# pcb_univ_3-_2-7_-_5-0_-x-rev3.net
KiCad netlist of a schematic drawn in EAGLE
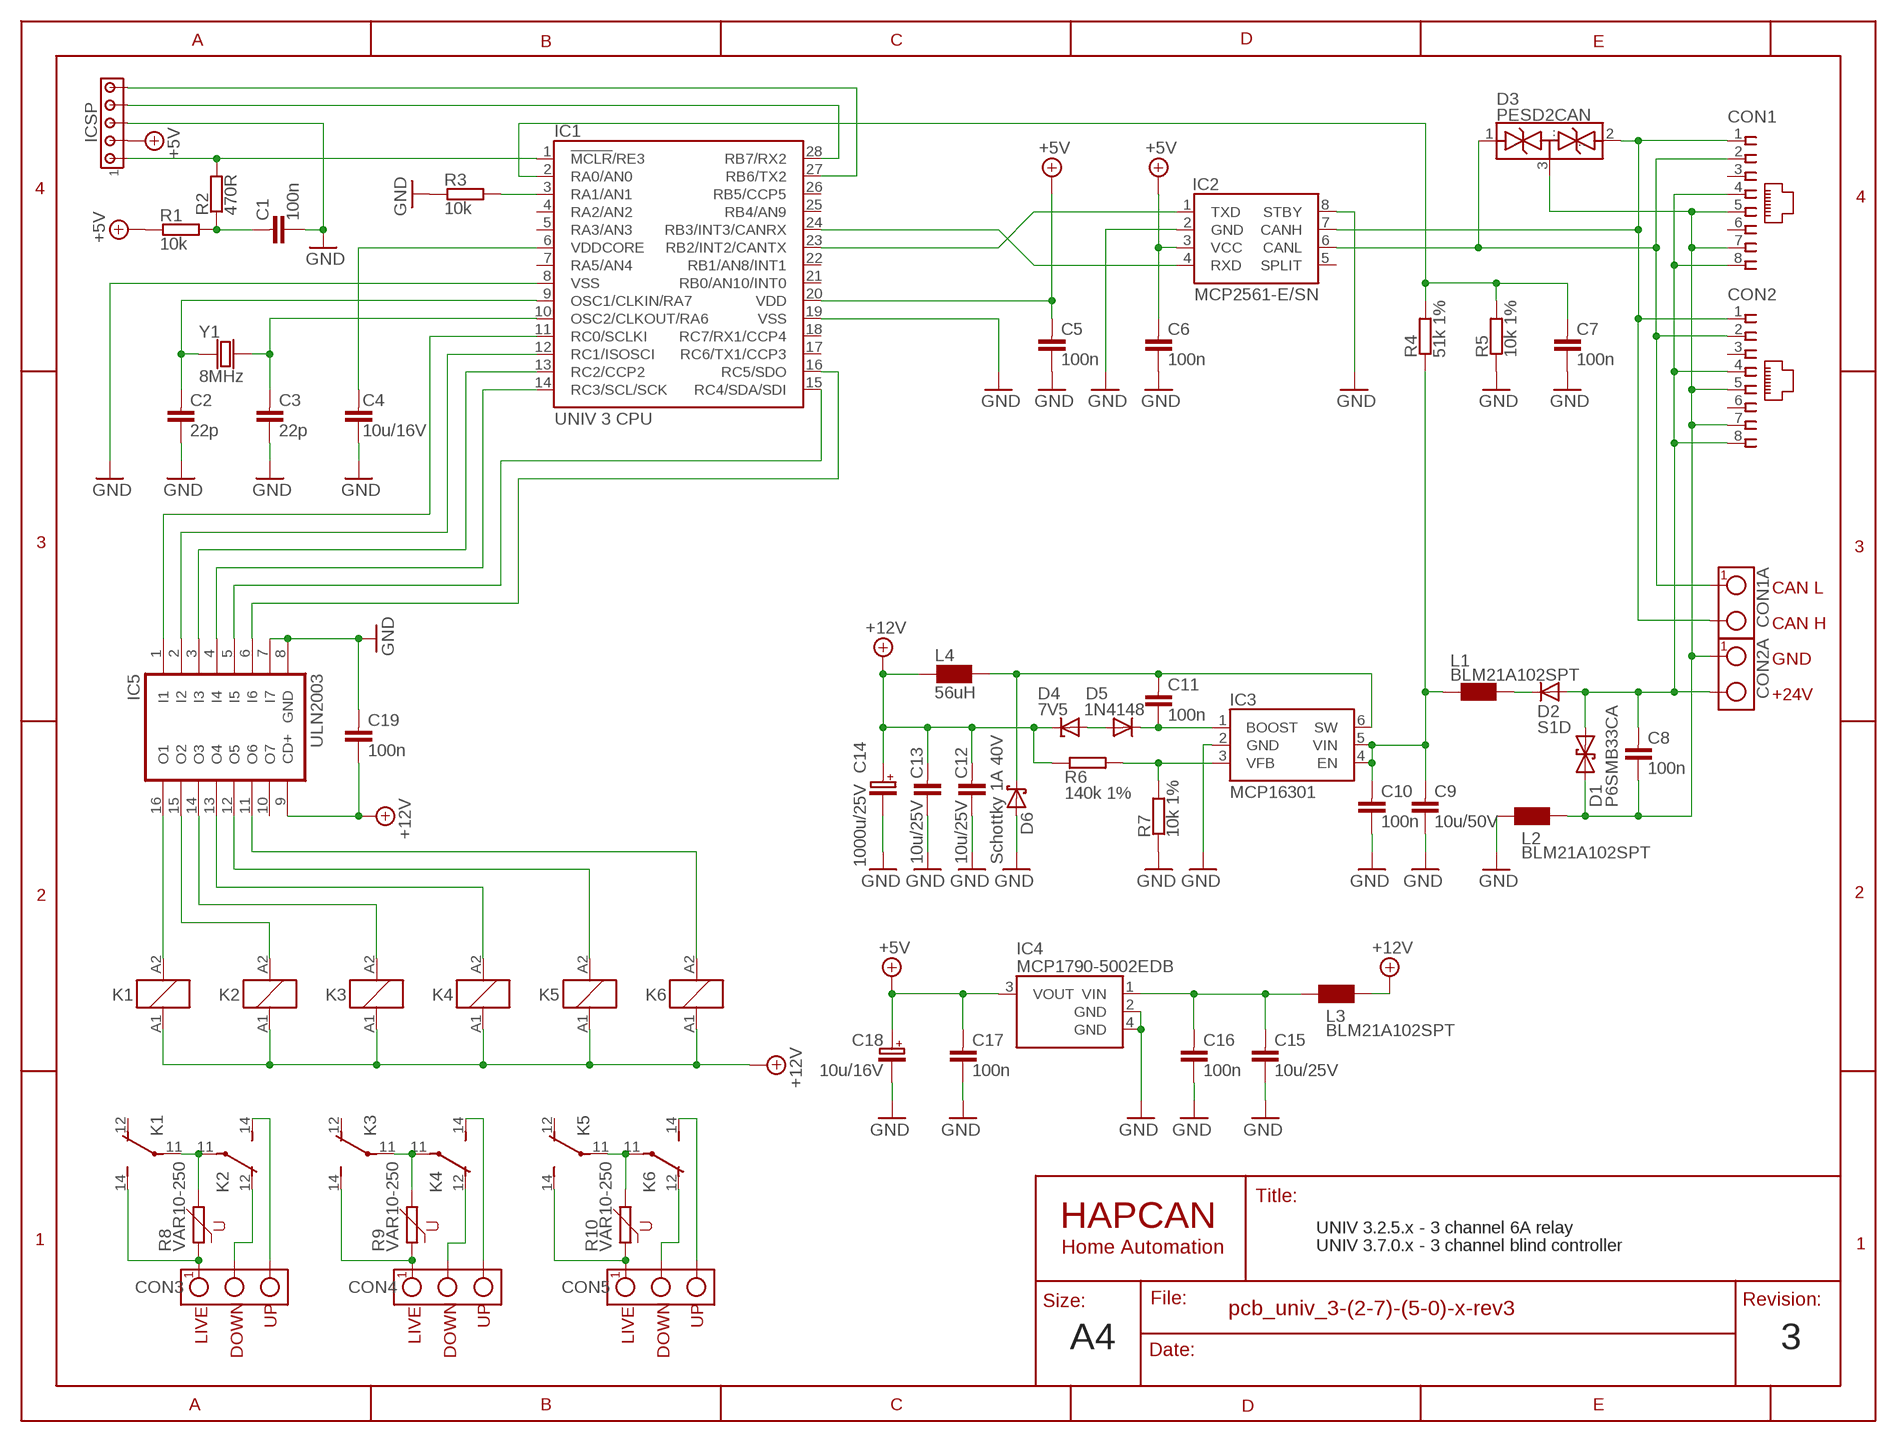
[diagram p0: schematic, sheet 1]

(export (version "E")
  (design (tool "Eeschema 10.0.6"))
  (components
    (comp (ref "C1")
      (value "100n")
      (footprint "eagle-import:0805")
      (libsource (lib "eagle-import") (part "CAPACITOR0805"))
    )
    (comp (ref "C2")
      (value "22p")
      (footprint "eagle-import:0805")
      (libsource (lib "eagle-import") (part "CAPACITOR0805"))
    )
    (comp (ref "C3")
      (value "22p")
      (footprint "eagle-import:0805")
      (libsource (lib "eagle-import") (part "CAPACITOR0805"))
    )
    (comp (ref "C4")
      (value "10u/16V")
      (footprint "eagle-import:0805")
      (libsource (lib "eagle-import") (part "CAPACITOR0805"))
    )
    (comp (ref "C5")
      (value "100n")
      (footprint "eagle-import:0805")
      (libsource (lib "eagle-import") (part "CAPACITOR0805"))
    )
    (comp (ref "C6")
      (value "100n")
      (footprint "eagle-import:0805")
      (libsource (lib "eagle-import") (part "CAPACITOR0805"))
    )
    (comp (ref "C7")
      (value "100n")
      (footprint "eagle-import:0805")
      (libsource (lib "eagle-import") (part "CAPACITOR0805"))
    )
    (comp (ref "C8")
      (value "100n")
      (footprint "eagle-import:0805")
      (libsource (lib "eagle-import") (part "CAPACITOR0805"))
    )
    (comp (ref "C9")
      (value "10u/50V")
      (footprint "eagle-import:1210")
      (libsource (lib "eagle-import") (part "CAPACITOR1210"))
    )
    (comp (ref "C10")
      (value "100n")
      (footprint "eagle-import:0805")
      (libsource (lib "eagle-import") (part "CAPACITOR0805"))
    )
    (comp (ref "C11")
      (value "100n")
      (footprint "eagle-import:0805")
      (libsource (lib "eagle-import") (part "CAPACITOR0805"))
    )
    (comp (ref "C12")
      (value "10u/25V")
      (footprint "eagle-import:1206")
      (libsource (lib "eagle-import") (part "CAPACITOR1206"))
    )
    (comp (ref "C13")
      (value "10u/25V")
      (footprint "eagle-import:1206")
      (libsource (lib "eagle-import") (part "CAPACITOR1206"))
    )
    (comp (ref "C14")
      (value "1000u/25V")
      (footprint "eagle-import:CAP-5X10.5")
      (libsource (lib "eagle-import") (part "CAPACITOR-POLARIZED-5X10.5"))
    )
    (comp (ref "C15")
      (value "10u/25V")
      (footprint "eagle-import:1206")
      (libsource (lib "eagle-import") (part "CAPACITOR1206"))
    )
    (comp (ref "C16")
      (value "100n")
      (footprint "eagle-import:0805")
      (libsource (lib "eagle-import") (part "CAPACITOR0805"))
    )
    (comp (ref "C17")
      (value "100n")
      (footprint "eagle-import:0805")
      (libsource (lib "eagle-import") (part "CAPACITOR0805"))
    )
    (comp (ref "C18")
      (value "10u/16V")
      (footprint "eagle-import:SMC_B")
      (libsource (lib "eagle-import") (part "CAPACITOR-POLARIZED-SMC_B"))
    )
    (comp (ref "C19")
      (value "100n")
      (footprint "eagle-import:0805")
      (libsource (lib "eagle-import") (part "CAPACITOR0805"))
    )
    (comp (ref "CON1")
      (value "RJ45-SOCKET")
      (footprint "eagle-import:RJ45-PCB-SOCKET")
      (libsource (lib "eagle-import") (part "RJ45-SOCKET"))
    )
    (comp (ref "CON1A")
      (value "TERMINAL-2")
      (footprint "eagle-import:ARK2-5X10,5MM")
      (libsource (lib "eagle-import") (part "TERMINAL-2-5X10,5MM"))
    )
    (comp (ref "CON2")
      (value "RJ45-SOCKET")
      (footprint "eagle-import:RJ45-PCB-SOCKET")
      (libsource (lib "eagle-import") (part "RJ45-SOCKET"))
    )
    (comp (ref "CON2A")
      (value "TERMINAL-2")
      (footprint "eagle-import:ARK2-5X10,5MM")
      (libsource (lib "eagle-import") (part "TERMINAL-2-5X10,5MM"))
    )
    (comp (ref "CON3")
      (value "TERMINAL-3-5X10.5MM")
      (footprint "eagle-import:ARK3-5X10.5MM")
      (libsource (lib "eagle-import") (part "TERMINAL-3-5X10.5MM"))
    )
    (comp (ref "CON4")
      (value "TERMINAL-3-5X10.5MM")
      (footprint "eagle-import:ARK3-5X10.5MM")
      (libsource (lib "eagle-import") (part "TERMINAL-3-5X10.5MM"))
    )
    (comp (ref "CON5")
      (value "TERMINAL-3-5X10.5MM")
      (footprint "eagle-import:ARK3-5X10.5MM")
      (libsource (lib "eagle-import") (part "TERMINAL-3-5X10.5MM"))
    )
    (comp (ref "D1")
      (value "P6SMB33CA")
      (footprint "eagle-import:DO-214_TRANSIL2")
      (libsource (lib "eagle-import") (part "DIODE_TRANSIL2"))
    )
    (comp (ref "D2")
      (value "S1D")
      (footprint "eagle-import:DO-214")
      (libsource (lib "eagle-import") (part "DIODE_DO-214"))
    )
    (comp (ref "D3")
      (value "PESD2CAN")
      (footprint "eagle-import:SOT-23")
      (libsource (lib "eagle-import") (part "PESD2CANSOT-23"))
    )
    (comp (ref "D4")
      (value "7V5")
      (footprint "eagle-import:SOD-80")
      (libsource (lib "eagle-import") (part "DIODE_ZENER_SOD-80"))
    )
    (comp (ref "D5")
      (value "1N4148")
      (footprint "eagle-import:0805")
      (libsource (lib "eagle-import") (part "DIODE_0805"))
    )
    (comp (ref "D6")
      (value "Schottky 1A 40V")
      (footprint "eagle-import:DO-214")
      (libsource (lib "eagle-import") (part "DIODE_TRANSIL1_DO214"))
    )
    (comp (ref "IC1")
      (value "UNIV 3 CPU")
      (footprint "eagle-import:UNIV3CPU")
      (libsource (lib "eagle-import") (part "UNIV3CPU-I/SO"))
    )
    (comp (ref "IC2")
      (value "MCP2561-E/SN")
      (footprint "eagle-import:SO-08")
      (libsource (lib "eagle-import") (part "MCP2561-E/SN"))
    )
    (comp (ref "IC3")
      (value "MCP16301")
      (footprint "eagle-import:SOT-23-6")
      (libsource (lib "eagle-import") (part "MCP16301SOT23-6"))
    )
    (comp (ref "IC4")
      (value "MCP1790-5002EDB")
      (footprint "eagle-import:SOT-223")
      (libsource (lib "eagle-import") (part "MCP1826SOT223-3"))
    )
    (comp (ref "IC5")
      (value "ULN2003")
      (footprint "eagle-import:SO-16")
      (libsource (lib "eagle-import") (part "ULN2003"))
    )
    (comp (ref "ICSP")
      (value "HEADER5")
      (footprint "eagle-import:SIP-5")
      (libsource (lib "eagle-import") (part "HEADER5"))
    )
    (comp (ref "K1")
      (value "RELAY_SNR_SPDTV")
      (footprint "eagle-import:RELAY_SNR_SPDT_V")
      (libsource (lib "eagle-import") (part "RELAY_SNR_SPDTV"))
    )
    (comp (ref "K2")
      (value "RELAY_SNR_SPDTV")
      (footprint "eagle-import:RELAY_SNR_SPDT_V")
      (libsource (lib "eagle-import") (part "RELAY_SNR_SPDTV"))
    )
    (comp (ref "K3")
      (value "RELAY_SNR_SPDTV")
      (footprint "eagle-import:RELAY_SNR_SPDT_V")
      (libsource (lib "eagle-import") (part "RELAY_SNR_SPDTV"))
    )
    (comp (ref "K4")
      (value "RELAY_SNR_SPDTV")
      (footprint "eagle-import:RELAY_SNR_SPDT_V")
      (libsource (lib "eagle-import") (part "RELAY_SNR_SPDTV"))
    )
    (comp (ref "K5")
      (value "RELAY_SNR_SPDTV")
      (footprint "eagle-import:RELAY_SNR_SPDT_V")
      (libsource (lib "eagle-import") (part "RELAY_SNR_SPDTV"))
    )
    (comp (ref "K6")
      (value "RELAY_SNR_SPDTV")
      (footprint "eagle-import:RELAY_SNR_SPDT_V")
      (libsource (lib "eagle-import") (part "RELAY_SNR_SPDTV"))
    )
    (comp (ref "L1")
      (value "BLM21A102SPT")
      (footprint "eagle-import:0805")
      (libsource (lib "eagle-import") (part "CHOKE0805"))
    )
    (comp (ref "L2")
      (value "BLM21A102SPT")
      (footprint "eagle-import:0805")
      (libsource (lib "eagle-import") (part "CHOKE0805"))
    )
    (comp (ref "L3")
      (value "BLM21A102SPT")
      (footprint "eagle-import:0805")
      (libsource (lib "eagle-import") (part "CHOKE0805"))
    )
    (comp (ref "L4")
      (value "56uH")
      (footprint "eagle-import:CHOKE-DER0705")
      (libsource (lib "eagle-import") (part "CHOKEDER0705"))
    )
    (comp (ref "R1")
      (value "10k")
      (footprint "eagle-import:0805")
      (libsource (lib "eagle-import") (part "RESISTOR0805"))
    )
    (comp (ref "R2")
      (value "470R")
      (footprint "eagle-import:0805")
      (libsource (lib "eagle-import") (part "RESISTOR0805"))
    )
    (comp (ref "R3")
      (value "10k")
      (footprint "eagle-import:0805")
      (libsource (lib "eagle-import") (part "RESISTOR0805"))
    )
    (comp (ref "R4")
      (value "51k 1%")
      (footprint "eagle-import:0805")
      (libsource (lib "eagle-import") (part "RESISTOR0805"))
    )
    (comp (ref "R5")
      (value "10k 1%")
      (footprint "eagle-import:0805")
      (libsource (lib "eagle-import") (part "RESISTOR0805"))
    )
    (comp (ref "R6")
      (value "140k 1%")
      (footprint "eagle-import:0805")
      (libsource (lib "eagle-import") (part "RESISTOR0805"))
    )
    (comp (ref "R7")
      (value "10k 1%")
      (footprint "eagle-import:0805")
      (libsource (lib "eagle-import") (part "RESISTOR0805"))
    )
    (comp (ref "R8")
      (value "VAR10-250")
      (footprint "eagle-import:VARISTOR1")
      (libsource (lib "eagle-import") (part "VARISTOR7.5MM-1"))
    )
    (comp (ref "R9")
      (value "VAR10-250")
      (footprint "eagle-import:VARISTOR1")
      (libsource (lib "eagle-import") (part "VARISTOR7.5MM-1"))
    )
    (comp (ref "R10")
      (value "VAR10-250")
      (footprint "eagle-import:VARISTOR1")
      (libsource (lib "eagle-import") (part "VARISTOR7.5MM-1"))
    )
    (comp (ref "Y1")
      (value "8MHz")
      (footprint "eagle-import:CRYSTAL-HC49V")
      (libsource (lib "eagle-import") (part "CRYSTAL-HC49V"))
    )
  )
  (nets
    (net (code "1") (name "+5V") (class "Default")
      (node (ref "C17") (pin "1") (pinfunction "1_1") (pintype "passive"))
      (node (ref "C18") (pin "+") (pinfunction "1_+") (pintype "passive"))
      (node (ref "C5") (pin "1") (pinfunction "1_1") (pintype "passive"))
      (node (ref "C6") (pin "1") (pinfunction "1_1") (pintype "passive"))
      (node (ref "IC1") (pin "20") (pinfunction "VDD_20") (pintype "bidirectional"))
      (node (ref "IC2") (pin "3") (pinfunction "VCC_3") (pintype "bidirectional"))
      (node (ref "IC4") (pin "3") (pinfunction "VOUT_3") (pintype "bidirectional"))
      (node (ref "ICSP") (pin "2") (pinfunction "2_2") (pintype "passive"))
      (node (ref "R1") (pin "1") (pinfunction "1_1") (pintype "passive"))
    )
    (net (code "2") (name "+12V") (class "Default")
      (node (ref "C12") (pin "1") (pinfunction "1_1") (pintype "passive"))
      (node (ref "C13") (pin "1") (pinfunction "1_1") (pintype "passive"))
      (node (ref "C14") (pin "+") (pinfunction "1_+") (pintype "passive"))
      (node (ref "C19") (pin "2") (pinfunction "2_2") (pintype "passive"))
      (node (ref "D4") (pin "C") (pinfunction "C_C") (pintype "passive"))
      (node (ref "IC5") (pin "9") (pinfunction "CD+_9") (pintype "passive"))
      (node (ref "K1") (pin "A1") (pinfunction "1_A1") (pintype "passive"))
      (node (ref "K2") (pin "A1") (pinfunction "1_A1") (pintype "passive"))
      (node (ref "K3") (pin "A1") (pinfunction "1_A1") (pintype "passive"))
      (node (ref "K4") (pin "A1") (pinfunction "1_A1") (pintype "passive"))
      (node (ref "K5") (pin "A1") (pinfunction "1_A1") (pintype "passive"))
      (node (ref "K6") (pin "A1") (pinfunction "1_A1") (pintype "passive"))
      (node (ref "L3") (pin "2") (pinfunction "2_2") (pintype "passive"))
      (node (ref "L4") (pin "1") (pinfunction "1_1") (pintype "passive"))
      (node (ref "R6") (pin "1") (pinfunction "1_1") (pintype "passive"))
    )
    (net (code "3") (name "GND") (class "Default")
      (node (ref "C1") (pin "2") (pinfunction "2_2") (pintype "passive"))
      (node (ref "C10") (pin "2") (pinfunction "2_2") (pintype "passive"))
      (node (ref "C12") (pin "2") (pinfunction "2_2") (pintype "passive"))
      (node (ref "C13") (pin "2") (pinfunction "2_2") (pintype "passive"))
      (node (ref "C14") (pin "-") (pinfunction "2_-") (pintype "passive"))
      (node (ref "C15") (pin "2") (pinfunction "2_2") (pintype "passive"))
      (node (ref "C16") (pin "2") (pinfunction "2_2") (pintype "passive"))
      (node (ref "C17") (pin "2") (pinfunction "2_2") (pintype "passive"))
      (node (ref "C18") (pin "-") (pinfunction "2_-") (pintype "passive"))
      (node (ref "C19") (pin "1") (pinfunction "1_1") (pintype "passive"))
      (node (ref "C2") (pin "2") (pinfunction "2_2") (pintype "passive"))
      (node (ref "C3") (pin "2") (pinfunction "2_2") (pintype "passive"))
      (node (ref "C4") (pin "2") (pinfunction "2_2") (pintype "passive"))
      (node (ref "C5") (pin "2") (pinfunction "2_2") (pintype "passive"))
      (node (ref "C6") (pin "2") (pinfunction "2_2") (pintype "passive"))
      (node (ref "C7") (pin "2") (pinfunction "2_2") (pintype "passive"))
      (node (ref "C9") (pin "2") (pinfunction "2_2") (pintype "passive"))
      (node (ref "D6") (pin "A") (pinfunction "A_A") (pintype "passive"))
      (node (ref "IC1") (pin "19") (pinfunction "VSS_19") (pintype "bidirectional"))
      (node (ref "IC1") (pin "8") (pinfunction "VSS_8") (pintype "bidirectional"))
      (node (ref "IC2") (pin "2") (pinfunction "GND_2") (pintype "bidirectional"))
      (node (ref "IC2") (pin "8") (pinfunction "STBY_8") (pintype "bidirectional"))
      (node (ref "IC3") (pin "2") (pinfunction "GND_2") (pintype "bidirectional"))
      (node (ref "IC4") (pin "2") (pinfunction "GND_2") (pintype "bidirectional"))
      (node (ref "IC4") (pin "4") (pinfunction "GND_4") (pintype "bidirectional"))
      (node (ref "IC5") (pin "7") (pinfunction "I7_7") (pintype "input"))
      (node (ref "IC5") (pin "8") (pinfunction "GND_8") (pintype "power_in"))
      (node (ref "ICSP") (pin "3") (pinfunction "3_3") (pintype "passive"))
      (node (ref "L2") (pin "1") (pinfunction "1_1") (pintype "passive"))
      (node (ref "R3") (pin "1") (pinfunction "1_1") (pintype "passive"))
      (node (ref "R5") (pin "1") (pinfunction "1_1") (pintype "passive"))
      (node (ref "R7") (pin "1") (pinfunction "1_1") (pintype "passive"))
    )
    (net (code "4") (name "Net-(C1-Pad1)") (class "Default")
      (node (ref "C1") (pin "1") (pinfunction "1_1") (pintype "passive"))
      (node (ref "R1") (pin "2") (pinfunction "2_2") (pintype "passive"))
      (node (ref "R2") (pin "1") (pinfunction "1_1") (pintype "passive"))
    )
    (net (code "5") (name "Net-(D1-1)") (class "Default")
      (node (ref "C8") (pin "2") (pinfunction "2_2") (pintype "passive"))
      (node (ref "CON1") (pin "5") (pinfunction "5_5") (pintype "passive"))
      (node (ref "CON1") (pin "7") (pinfunction "7_7") (pintype "passive"))
      (node (ref "CON2") (pin "5") (pinfunction "5_5") (pintype "passive"))
      (node (ref "CON2") (pin "7") (pinfunction "7_7") (pintype "passive"))
      (node (ref "CON2A") (pin "1") (pinfunction "1_1") (pintype "passive"))
      (node (ref "D1") (pin "A") (pinfunction "1_A") (pintype "passive"))
      (node (ref "D3") (pin "3") (pinfunction "..._3") (pintype "bidirectional"))
      (node (ref "L2") (pin "2") (pinfunction "2_2") (pintype "passive"))
    )
    (net (code "6") (name "Net-(D1-2)") (class "Default")
      (node (ref "C8") (pin "1") (pinfunction "1_1") (pintype "passive"))
      (node (ref "CON1") (pin "4") (pinfunction "4_4") (pintype "passive"))
      (node (ref "CON1") (pin "8") (pinfunction "8_8") (pintype "passive"))
      (node (ref "CON2") (pin "4") (pinfunction "4_4") (pintype "passive"))
      (node (ref "CON2") (pin "8") (pinfunction "8_8") (pintype "passive"))
      (node (ref "CON2A") (pin "2") (pinfunction "2_2") (pintype "passive"))
      (node (ref "D1") (pin "C") (pinfunction "2_C") (pintype "passive"))
      (node (ref "D2") (pin "A") (pinfunction "A_A") (pintype "passive"))
    )
    (net (code "7") (name "Net-(D2-PadC)") (class "Default")
      (node (ref "D2") (pin "C") (pinfunction "C_C") (pintype "passive"))
      (node (ref "L1") (pin "2") (pinfunction "2_2") (pintype "passive"))
    )
    (net (code "8") (name "Net-(D3-.)") (class "Default")
      (node (ref "CON1") (pin "2") (pinfunction "2_2") (pintype "passive"))
      (node (ref "CON1A") (pin "1") (pinfunction "1_1") (pintype "passive"))
      (node (ref "CON2") (pin "2") (pinfunction "2_2") (pintype "passive"))
      (node (ref "D3") (pin "1") (pinfunction "._1") (pintype "bidirectional"))
      (node (ref "IC2") (pin "6") (pinfunction "CANL_6") (pintype "bidirectional"))
    )
    (net (code "9") (name "Net-(D3-..)") (class "Default")
      (node (ref "CON1") (pin "1") (pinfunction "1_1") (pintype "passive"))
      (node (ref "CON1A") (pin "2") (pinfunction "2_2") (pintype "passive"))
      (node (ref "CON2") (pin "1") (pinfunction "1_1") (pintype "passive"))
      (node (ref "D3") (pin "2") (pinfunction ".._2") (pintype "bidirectional"))
      (node (ref "IC2") (pin "7") (pinfunction "CANH_7") (pintype "bidirectional"))
    )
    (net (code "10") (name "Net-(D5-A)") (class "Default")
      (node (ref "D4") (pin "A") (pinfunction "A_A") (pintype "passive"))
      (node (ref "D5") (pin "2") (pinfunction "A_2") (pintype "passive"))
    )
    (net (code "11") (name "Net-(D5-C)") (class "Default")
      (node (ref "C11") (pin "2") (pinfunction "2_2") (pintype "passive"))
      (node (ref "D5") (pin "1") (pinfunction "C_1") (pintype "passive"))
      (node (ref "IC3") (pin "1") (pinfunction "BOOST_1") (pintype "bidirectional"))
    )
    (net (code "12") (name "Net-(IC1-OSC1{slash}CLKIN{slash}RA7)") (class "Default")
      (node (ref "C2") (pin "1") (pinfunction "1_1") (pintype "passive"))
      (node (ref "IC1") (pin "9") (pinfunction "OSC1/CLKIN/RA7_9") (pintype "bidirectional"))
      (node (ref "Y1") (pin "1") (pinfunction "1_1") (pintype "passive"))
    )
    (net (code "13") (name "Net-(IC1-OSC2{slash}CLKOUT{slash}RA6)") (class "Default")
      (node (ref "C3") (pin "1") (pinfunction "1_1") (pintype "passive"))
      (node (ref "IC1") (pin "10") (pinfunction "OSC2/CLKOUT/RA6_10") (pintype "bidirectional"))
      (node (ref "Y1") (pin "2") (pinfunction "2_2") (pintype "passive"))
    )
    (net (code "14") (name "Net-(IC1-RA0{slash}AN0)") (class "Default")
      (node (ref "C7") (pin "1") (pinfunction "1_1") (pintype "passive"))
      (node (ref "IC1") (pin "2") (pinfunction "RA0/AN0_2") (pintype "bidirectional"))
      (node (ref "R4") (pin "2") (pinfunction "2_2") (pintype "passive"))
      (node (ref "R5") (pin "2") (pinfunction "2_2") (pintype "passive"))
    )
    (net (code "15") (name "Net-(IC1-RA1{slash}AN1)") (class "Default")
      (node (ref "IC1") (pin "3") (pinfunction "RA1/AN1_3") (pintype "bidirectional"))
      (node (ref "R3") (pin "2") (pinfunction "2_2") (pintype "passive"))
    )
    (net (code "16") (name "Net-(IC1-RB2{slash}INT2{slash}CANTX)") (class "Default")
      (node (ref "IC1") (pin "23") (pinfunction "RB2/INT2/CANTX_23") (pintype "bidirectional"))
      (node (ref "IC2") (pin "1") (pinfunction "TXD_1") (pintype "bidirectional"))
    )
    (net (code "17") (name "Net-(IC1-RB3{slash}INT3{slash}CANRX)") (class "Default")
      (node (ref "IC1") (pin "24") (pinfunction "RB3/INT3/CANRX_24") (pintype "bidirectional"))
      (node (ref "IC2") (pin "4") (pinfunction "RXD_4") (pintype "bidirectional"))
    )
    (net (code "18") (name "Net-(IC1-RB6{slash}TX2)") (class "Default")
      (node (ref "IC1") (pin "27") (pinfunction "RB6/TX2_27") (pintype "bidirectional"))
      (node (ref "ICSP") (pin "5") (pinfunction "5_5") (pintype "passive"))
    )
    (net (code "19") (name "Net-(IC1-RB7{slash}RX2)") (class "Default")
      (node (ref "IC1") (pin "28") (pinfunction "RB7/RX2_28") (pintype "bidirectional"))
      (node (ref "ICSP") (pin "4") (pinfunction "4_4") (pintype "passive"))
    )
    (net (code "20") (name "Net-(IC1-RC0{slash}SCLKI)") (class "Default")
      (node (ref "IC1") (pin "11") (pinfunction "RC0/SCLKI_11") (pintype "bidirectional"))
      (node (ref "IC5") (pin "1") (pinfunction "I1_1") (pintype "input"))
    )
    (net (code "21") (name "Net-(IC1-RC1{slash}ISOSCI)") (class "Default")
      (node (ref "IC1") (pin "12") (pinfunction "RC1/ISOSCI_12") (pintype "bidirectional"))
      (node (ref "IC5") (pin "2") (pinfunction "I2_2") (pintype "input"))
    )
    (net (code "22") (name "Net-(IC1-RC2{slash}CCP2)") (class "Default")
      (node (ref "IC1") (pin "13") (pinfunction "RC2/CCP2_13") (pintype "bidirectional"))
      (node (ref "IC5") (pin "3") (pinfunction "I3_3") (pintype "input"))
    )
    (net (code "23") (name "Net-(IC1-RC3{slash}SCL{slash}SCK)") (class "Default")
      (node (ref "IC1") (pin "14") (pinfunction "RC3/SCL/SCK_14") (pintype "bidirectional"))
      (node (ref "IC5") (pin "4") (pinfunction "I4_4") (pintype "input"))
    )
    (net (code "24") (name "Net-(IC1-RC4{slash}SDA{slash}SDI)") (class "Default")
      (node (ref "IC1") (pin "15") (pinfunction "RC4/SDA/SDI_15") (pintype "bidirectional"))
      (node (ref "IC5") (pin "5") (pinfunction "I5_5") (pintype "input"))
    )
    (net (code "25") (name "Net-(IC1-RC5{slash}SDO)") (class "Default")
      (node (ref "IC1") (pin "16") (pinfunction "RC5/SDO_16") (pintype "bidirectional"))
      (node (ref "IC5") (pin "6") (pinfunction "I6_6") (pintype "input"))
    )
    (net (code "26") (name "Net-(IC1-VDDCORE)") (class "Default")
      (node (ref "C4") (pin "1") (pinfunction "1_1") (pintype "passive"))
      (node (ref "IC1") (pin "6") (pinfunction "VDDCORE_6") (pintype "bidirectional"))
    )
    (net (code "27") (name "Net-(IC1-~{MCLR}{slash}RE3)") (class "Default")
      (node (ref "IC1") (pin "1") (pinfunction "~{MCLR}/RE3_1") (pintype "bidirectional"))
      (node (ref "ICSP") (pin "1") (pinfunction "1_1") (pintype "passive"))
      (node (ref "R2") (pin "2") (pinfunction "2_2") (pintype "passive"))
    )
    (net (code "28") (name "Net-(IC3-EN)") (class "Default")
      (node (ref "C10") (pin "1") (pinfunction "1_1") (pintype "passive"))
      (node (ref "C9") (pin "1") (pinfunction "1_1") (pintype "passive"))
      (node (ref "IC3") (pin "4") (pinfunction "EN_4") (pintype "bidirectional"))
      (node (ref "IC3") (pin "5") (pinfunction "VIN_5") (pintype "bidirectional"))
      (node (ref "L1") (pin "1") (pinfunction "1_1") (pintype "passive"))
      (node (ref "R4") (pin "1") (pinfunction "1_1") (pintype "passive"))
    )
    (net (code "29") (name "Net-(IC3-SW)") (class "Default")
      (node (ref "C11") (pin "1") (pinfunction "1_1") (pintype "passive"))
      (node (ref "D6") (pin "C") (pinfunction "C_C") (pintype "passive"))
      (node (ref "IC3") (pin "6") (pinfunction "SW_6") (pintype "bidirectional"))
      (node (ref "L4") (pin "2") (pinfunction "2_2") (pintype "passive"))
    )
    (net (code "30") (name "Net-(IC3-VFB)") (class "Default")
      (node (ref "IC3") (pin "3") (pinfunction "VFB_3") (pintype "bidirectional"))
      (node (ref "R6") (pin "2") (pinfunction "2_2") (pintype "passive"))
      (node (ref "R7") (pin "2") (pinfunction "2_2") (pintype "passive"))
    )
    (net (code "31") (name "Net-(IC4-VIN)") (class "Default")
      (node (ref "C15") (pin "1") (pinfunction "1_1") (pintype "passive"))
      (node (ref "C16") (pin "1") (pinfunction "1_1") (pintype "passive"))
      (node (ref "IC4") (pin "1") (pinfunction "VIN_1") (pintype "bidirectional"))
      (node (ref "L3") (pin "1") (pinfunction "1_1") (pintype "passive"))
    )
    (net (code "32") (name "Net-(IC5-O1)") (class "Default")
      (node (ref "IC5") (pin "16") (pinfunction "O1_16") (pintype "open_collector"))
      (node (ref "K1") (pin "A2") (pinfunction "2_A2") (pintype "passive"))
    )
    (net (code "33") (name "Net-(IC5-O2)") (class "Default")
      (node (ref "IC5") (pin "15") (pinfunction "O2_15") (pintype "open_collector"))
      (node (ref "K2") (pin "A2") (pinfunction "2_A2") (pintype "passive"))
    )
    (net (code "34") (name "Net-(IC5-O3)") (class "Default")
      (node (ref "IC5") (pin "14") (pinfunction "O3_14") (pintype "open_collector"))
      (node (ref "K3") (pin "A2") (pinfunction "2_A2") (pintype "passive"))
    )
    (net (code "35") (name "Net-(IC5-O4)") (class "Default")
      (node (ref "IC5") (pin "13") (pinfunction "O4_13") (pintype "open_collector"))
      (node (ref "K4") (pin "A2") (pinfunction "2_A2") (pintype "passive"))
    )
    (net (code "36") (name "Net-(IC5-O5)") (class "Default")
      (node (ref "IC5") (pin "12") (pinfunction "O5_12") (pintype "open_collector"))
      (node (ref "K5") (pin "A2") (pinfunction "2_A2") (pintype "passive"))
    )
    (net (code "37") (name "Net-(IC5-O6)") (class "Default")
      (node (ref "IC5") (pin "11") (pinfunction "O6_11") (pintype "open_collector"))
      (node (ref "K6") (pin "A2") (pinfunction "2_A2") (pintype "passive"))
    )
    (net (code "38") (name "Net-(K1B-COM)") (class "Default")
      (node (ref "K1") (pin "11") (pinfunction "COM_11") (pintype "passive"))
      (node (ref "K2") (pin "11") (pinfunction "COM_11") (pintype "passive"))
      (node (ref "R8") (pin "2") (pinfunction "2_2") (pintype "passive"))
    )
    (net (code "39") (name "Net-(K1B-NO)") (class "Default")
      (node (ref "CON3") (pin "1") (pinfunction "1_1") (pintype "passive"))
      (node (ref "K1") (pin "14") (pinfunction "NO_14") (pintype "passive"))
      (node (ref "R8") (pin "1") (pinfunction "1_1") (pintype "passive"))
    )
    (net (code "40") (name "Net-(K2B-NC)") (class "Default")
      (node (ref "CON3") (pin "2") (pinfunction "2_2") (pintype "passive"))
      (node (ref "K2") (pin "12") (pinfunction "NC_12") (pintype "passive"))
    )
    (net (code "41") (name "Net-(K2B-NO)") (class "Default")
      (node (ref "CON3") (pin "3") (pinfunction "3_3") (pintype "passive"))
      (node (ref "K2") (pin "14") (pinfunction "NO_14") (pintype "passive"))
    )
    (net (code "42") (name "Net-(K3B-COM)") (class "Default")
      (node (ref "K3") (pin "11") (pinfunction "COM_11") (pintype "passive"))
      (node (ref "K4") (pin "11") (pinfunction "COM_11") (pintype "passive"))
      (node (ref "R9") (pin "2") (pinfunction "2_2") (pintype "passive"))
    )
    (net (code "43") (name "Net-(K3B-NO)") (class "Default")
      (node (ref "CON4") (pin "1") (pinfunction "1_1") (pintype "passive"))
      (node (ref "K3") (pin "14") (pinfunction "NO_14") (pintype "passive"))
      (node (ref "R9") (pin "1") (pinfunction "1_1") (pintype "passive"))
    )
    (net (code "44") (name "Net-(K4B-NC)") (class "Default")
      (node (ref "CON4") (pin "2") (pinfunction "2_2") (pintype "passive"))
      (node (ref "K4") (pin "12") (pinfunction "NC_12") (pintype "passive"))
    )
    (net (code "45") (name "Net-(K4B-NO)") (class "Default")
      (node (ref "CON4") (pin "3") (pinfunction "3_3") (pintype "passive"))
      (node (ref "K4") (pin "14") (pinfunction "NO_14") (pintype "passive"))
    )
    (net (code "46") (name "Net-(K5B-COM)") (class "Default")
      (node (ref "K5") (pin "11") (pinfunction "COM_11") (pintype "passive"))
      (node (ref "K6") (pin "11") (pinfunction "COM_11") (pintype "passive"))
      (node (ref "R10") (pin "2") (pinfunction "2_2") (pintype "passive"))
    )
    (net (code "47") (name "Net-(K5B-NO)") (class "Default")
      (node (ref "CON5") (pin "1") (pinfunction "1_1") (pintype "passive"))
      (node (ref "K5") (pin "14") (pinfunction "NO_14") (pintype "passive"))
      (node (ref "R10") (pin "1") (pinfunction "1_1") (pintype "passive"))
    )
    (net (code "48") (name "Net-(K6B-NC)") (class "Default")
      (node (ref "CON5") (pin "2") (pinfunction "2_2") (pintype "passive"))
      (node (ref "K6") (pin "12") (pinfunction "NC_12") (pintype "passive"))
    )
    (net (code "49") (name "Net-(K6B-NO)") (class "Default")
      (node (ref "CON5") (pin "3") (pinfunction "3_3") (pintype "passive"))
      (node (ref "K6") (pin "14") (pinfunction "NO_14") (pintype "passive"))
    )
    (net (code "50") (name "unconnected-(CON1-Pad3)") (class "Default")
      (node (ref "CON1") (pin "3") (pinfunction "3_3") (pintype "passive"))
    )
    (net (code "51") (name "unconnected-(CON1-Pad6)") (class "Default")
      (node (ref "CON1") (pin "6") (pinfunction "6_6") (pintype "passive"))
    )
    (net (code "52") (name "unconnected-(CON2-Pad3)") (class "Default")
      (node (ref "CON2") (pin "3") (pinfunction "3_3") (pintype "passive"))
    )
    (net (code "53") (name "unconnected-(CON2-Pad6)") (class "Default")
      (node (ref "CON2") (pin "6") (pinfunction "6_6") (pintype "passive"))
    )
    (net (code "54") (name "unconnected-(IC1-RA2{slash}AN2-Pad4)") (class "Default")
      (node (ref "IC1") (pin "4") (pinfunction "RA2/AN2_4") (pintype "bidirectional"))
    )
    (net (code "55") (name "unconnected-(IC1-RA3{slash}AN3-Pad5)") (class "Default")
      (node (ref "IC1") (pin "5") (pinfunction "RA3/AN3_5") (pintype "bidirectional"))
    )
    (net (code "56") (name "unconnected-(IC1-RA5{slash}AN4-Pad7)") (class "Default")
      (node (ref "IC1") (pin "7") (pinfunction "RA5/AN4_7") (pintype "bidirectional"))
    )
    (net (code "57") (name "unconnected-(IC1-RB0{slash}AN10{slash}INT0-Pad21)") (class "Default")
      (node (ref "IC1") (pin "21") (pinfunction "RB0/AN10/INT0_21") (pintype "bidirectional"))
    )
    (net (code "58") (name "unconnected-(IC1-RB1{slash}AN8{slash}INT1-Pad22)") (class "Default")
      (node (ref "IC1") (pin "22") (pinfunction "RB1/AN8/INT1_22") (pintype "bidirectional"))
    )
    (net (code "59") (name "unconnected-(IC1-RB4{slash}AN9-Pad25)") (class "Default")
      (node (ref "IC1") (pin "25") (pinfunction "RB4/AN9_25") (pintype "bidirectional"))
    )
    (net (code "60") (name "unconnected-(IC1-RB5{slash}CCP5-Pad26)") (class "Default")
      (node (ref "IC1") (pin "26") (pinfunction "RB5/CCP5_26") (pintype "bidirectional"))
    )
    (net (code "61") (name "unconnected-(IC1-RC6{slash}TX1{slash}CCP3-Pad17)") (class "Default")
      (node (ref "IC1") (pin "17") (pinfunction "RC6/TX1/CCP3_17") (pintype "bidirectional"))
    )
    (net (code "62") (name "unconnected-(IC1-RC7{slash}RX1{slash}CCP4-Pad18)") (class "Default")
      (node (ref "IC1") (pin "18") (pinfunction "RC7/RX1/CCP4_18") (pintype "bidirectional"))
    )
    (net (code "63") (name "unconnected-(IC2-SPLIT-Pad5)") (class "Default")
      (node (ref "IC2") (pin "5") (pinfunction "SPLIT_5") (pintype "bidirectional"))
    )
    (net (code "64") (name "unconnected-(IC5-O7-Pad10)") (class "Default")
      (node (ref "IC5") (pin "10") (pinfunction "O7_10") (pintype "open_collector"))
    )
    (net (code "65") (name "unconnected-(K1B-NC-Pad12)") (class "Default")
      (node (ref "K1") (pin "12") (pinfunction "NC_12") (pintype "passive"))
    )
    (net (code "66") (name "unconnected-(K3B-NC-Pad12)") (class "Default")
      (node (ref "K3") (pin "12") (pinfunction "NC_12") (pintype "passive"))
    )
    (net (code "67") (name "unconnected-(K5B-NC-Pad12)") (class "Default")
      (node (ref "K5") (pin "12") (pinfunction "NC_12") (pintype "passive"))
    )
  )
)
